# speech2.net
KiCad netlist of a schematic drawn in EAGLE
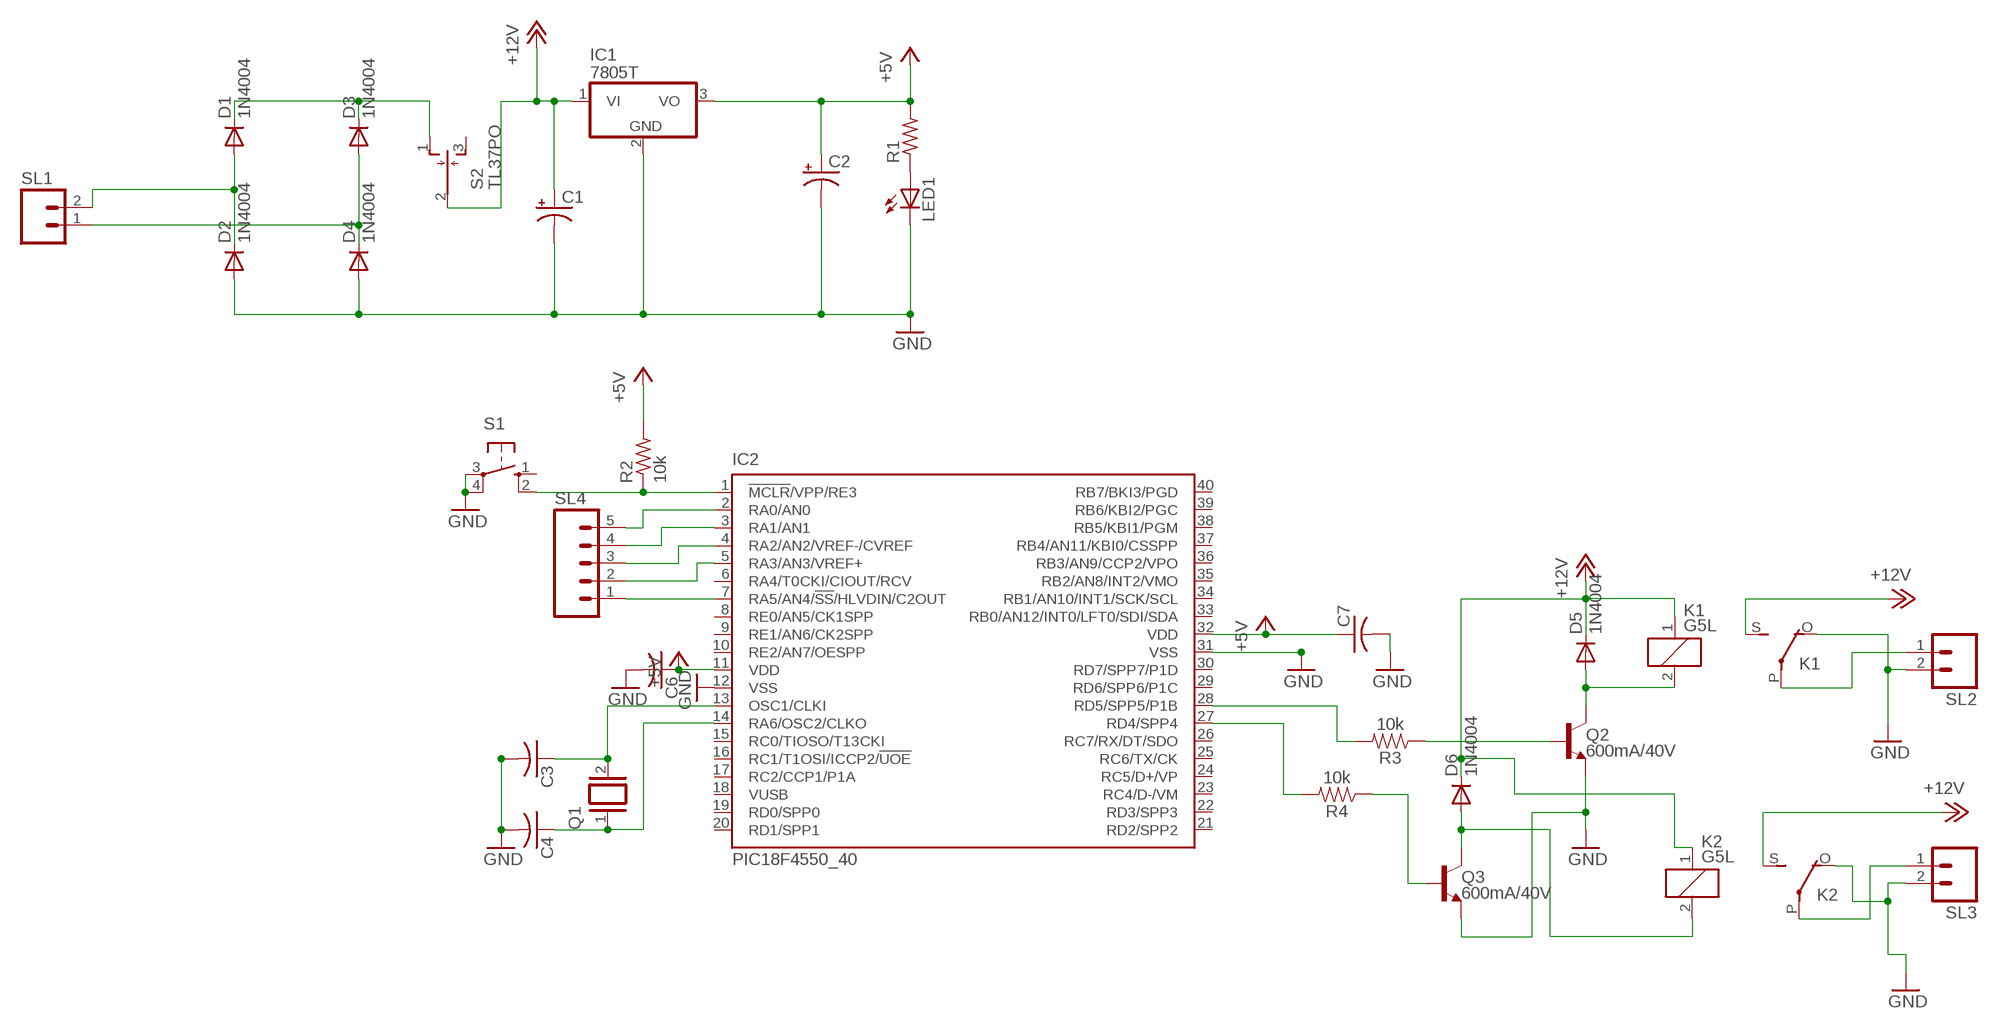
[diagram p0: schematic, sheet 1]

(export (version "E")
  (design (tool "Eeschema 10.0.6"))
  (components
    (comp (ref "C1")
      (value "CPOL-USE3.5-8")
      (footprint "eagle-import:E3,5-8")
      (libsource (lib "eagle-import") (part "CPOL-USE3.5-8"))
    )
    (comp (ref "C2")
      (value "CPOL-USE3.5-8")
      (footprint "eagle-import:E3,5-8")
      (libsource (lib "eagle-import") (part "CPOL-USE3.5-8"))
    )
    (comp (ref "C3")
      (value "C-US025-024X044")
      (footprint "eagle-import:C025-024X044")
      (libsource (lib "eagle-import") (part "C-US025-024X044"))
    )
    (comp (ref "C4")
      (value "C-US025-024X044")
      (footprint "eagle-import:C025-024X044")
      (libsource (lib "eagle-import") (part "C-US025-024X044"))
    )
    (comp (ref "C6")
      (value "C-US025-024X044")
      (footprint "eagle-import:C025-024X044")
      (libsource (lib "eagle-import") (part "C-US025-024X044"))
    )
    (comp (ref "C7")
      (value "C-US025-024X044")
      (footprint "eagle-import:C025-024X044")
      (libsource (lib "eagle-import") (part "C-US025-024X044"))
    )
    (comp (ref "D1")
      (value "1N4004")
      (footprint "eagle-import:DO41-10")
      (libsource (lib "eagle-import") (part "1N4004"))
    )
    (comp (ref "D2")
      (value "1N4004")
      (footprint "eagle-import:DO41-10")
      (libsource (lib "eagle-import") (part "1N4004"))
    )
    (comp (ref "D3")
      (value "1N4004")
      (footprint "eagle-import:DO41-10")
      (libsource (lib "eagle-import") (part "1N4004"))
    )
    (comp (ref "D4")
      (value "1N4004")
      (footprint "eagle-import:DO41-10")
      (libsource (lib "eagle-import") (part "1N4004"))
    )
    (comp (ref "D5")
      (value "1N4004")
      (footprint "eagle-import:DO41-10")
      (libsource (lib "eagle-import") (part "1N4004"))
    )
    (comp (ref "D6")
      (value "1N4004")
      (footprint "eagle-import:DO41-10")
      (libsource (lib "eagle-import") (part "1N4004"))
    )
    (comp (ref "IC1")
      (value "7805T")
      (footprint "eagle-import:TO220H")
      (libsource (lib "eagle-import") (part "78T05"))
    )
    (comp (ref "IC2")
      (value "PIC18F4550_40")
      (footprint "eagle-import:DIL40")
      (fields (field (name "MF") "MICROCHIP") (field (name "MPN") "PIC18F4550-I/P"))
      (libsource (lib "eagle-import") (part "PIC18F4_40550"))
    )
    (comp (ref "K1")
      (value "G5L")
      (footprint "eagle-import:G5LE")
      (libsource (lib "eagle-import") (part "G5L"))
    )
    (comp (ref "K2")
      (value "G5L")
      (footprint "eagle-import:G5LE")
      (libsource (lib "eagle-import") (part "G5L"))
    )
    (comp (ref "LED1")
      (value "LED5MM")
      (footprint "eagle-import:LED5MM")
      (libsource (lib "eagle-import") (part "LED5MM"))
    )
    (comp (ref "Q1")
      (value "XTAL/S")
      (footprint "eagle-import:QS")
      (libsource (lib "eagle-import") (part "XTAL/S"))
    )
    (comp (ref "Q2")
      (value "600mA/40V")
      (footprint "eagle-import:TO-92")
      (libsource (lib "eagle-import") (part "TRANS_NPN-P2N2222A"))
    )
    (comp (ref "Q3")
      (value "600mA/40V")
      (footprint "eagle-import:TO-92")
      (libsource (lib "eagle-import") (part "TRANS_NPN-P2N2222A"))
    )
    (comp (ref "R1")
      (value "R-US_0207/10")
      (footprint "eagle-import:0207_10")
      (libsource (lib "eagle-import") (part "R-US_0207/10"))
    )
    (comp (ref "R2")
      (value "10k")
      (footprint "eagle-import:0207_10")
      (libsource (lib "eagle-import") (part "R-US_0207/10"))
    )
    (comp (ref "R3")
      (value "10k")
      (footprint "eagle-import:AXIAL-0.3")
      (libsource (lib "eagle-import") (part "10KOHM-HORIZ-1/4W-1%"))
    )
    (comp (ref "R4")
      (value "10k")
      (footprint "eagle-import:AXIAL-0.3")
      (libsource (lib "eagle-import") (part "10KOHM-HORIZ-1/4W-1%"))
    )
    (comp (ref "S1")
      (value "10-XX")
      (footprint "eagle-import:B3F-10XX")
      (fields (field (name "MPN") "B3F-1000"))
      (libsource (lib "eagle-import") (part "10-XX"))
    )
    (comp (ref "S2")
      (value "TL37PO")
      (footprint "eagle-import:TL3XPO")
      (libsource (lib "eagle-import") (part "TL37PO"))
    )
    (comp (ref "SL1")
      (value "MA02")
      (footprint "eagle-import:02PA")
      (libsource (lib "eagle-import") (part "MA02"))
    )
    (comp (ref "SL2")
      (value "MA02")
      (footprint "eagle-import:02PA")
      (libsource (lib "eagle-import") (part "MA02"))
    )
    (comp (ref "SL3")
      (value "MA02")
      (footprint "eagle-import:02PA")
      (libsource (lib "eagle-import") (part "MA02"))
    )
    (comp (ref "SL4")
      (value "MA05")
      (footprint "eagle-import:05PA")
      (libsource (lib "eagle-import") (part "MA05"))
    )
  )
  (nets
    (net (code "1") (name "+5V") (class "Default")
      (node (ref "C2") (pin "+") (pinfunction "+_+") (pintype "passive"))
      (node (ref "C6") (pin "1") (pinfunction "1_1") (pintype "passive"))
      (node (ref "C7") (pin "1") (pinfunction "1_1") (pintype "passive"))
      (node (ref "IC1") (pin "3") (pinfunction "VO_3") (pintype "passive"))
      (node (ref "IC2") (pin "11") (pinfunction "VDD_11") (pintype "power_in"))
      (node (ref "IC2") (pin "32") (pinfunction "VDD_32") (pintype "power_in"))
      (node (ref "R1") (pin "2") (pinfunction "2_2") (pintype "passive"))
      (node (ref "R2") (pin "2") (pinfunction "2_2") (pintype "passive"))
    )
    (net (code "2") (name "+12V") (class "Default")
      (node (ref "C1") (pin "+") (pinfunction "+_+") (pintype "passive"))
      (node (ref "D5") (pin "C") (pinfunction "C_C") (pintype "passive"))
      (node (ref "D6") (pin "C") (pinfunction "C_C") (pintype "passive"))
      (node (ref "IC1") (pin "1") (pinfunction "VI_1") (pintype "input"))
      (node (ref "K1") (pin "1") (pinfunction "1_1") (pintype "passive"))
      (node (ref "K1") (pin "S") (pinfunction "S_S") (pintype "passive"))
      (node (ref "K2") (pin "1") (pinfunction "1_1") (pintype "passive"))
      (node (ref "K2") (pin "S") (pinfunction "S_S") (pintype "passive"))
      (node (ref "S2") (pin "2") (pinfunction "P_2") (pintype "passive"))
    )
    (net (code "3") (name "GND") (class "Default")
      (node (ref "C1") (pin "-") (pinfunction "-_-") (pintype "passive"))
      (node (ref "C2") (pin "-") (pinfunction "-_-") (pintype "passive"))
      (node (ref "C3") (pin "2") (pinfunction "2_2") (pintype "passive"))
      (node (ref "C4") (pin "2") (pinfunction "2_2") (pintype "passive"))
      (node (ref "C6") (pin "2") (pinfunction "2_2") (pintype "passive"))
      (node (ref "C7") (pin "2") (pinfunction "2_2") (pintype "passive"))
      (node (ref "D2") (pin "A") (pinfunction "A_A") (pintype "passive"))
      (node (ref "D4") (pin "A") (pinfunction "A_A") (pintype "passive"))
      (node (ref "IC1") (pin "2") (pinfunction "GND_2") (pintype "passive"))
      (node (ref "IC2") (pin "12") (pinfunction "VSS_12") (pintype "power_in"))
      (node (ref "IC2") (pin "31") (pinfunction "VSS_31") (pintype "power_in"))
      (node (ref "K1") (pin "O") (pinfunction "O_O") (pintype "passive"))
      (node (ref "K2") (pin "O") (pinfunction "O_O") (pintype "passive"))
      (node (ref "LED1") (pin "K") (pinfunction "C_K") (pintype "passive"))
      (node (ref "Q2") (pin "3") (pinfunction "E_3") (pintype "passive"))
      (node (ref "Q3") (pin "3") (pinfunction "E_3") (pintype "passive"))
      (node (ref "S1") (pin "3") (pinfunction "P_3") (pintype "passive"))
      (node (ref "S1") (pin "4") (pinfunction "P1_4") (pintype "passive"))
      (node (ref "SL2") (pin "2") (pinfunction "2_2") (pintype "passive"))
      (node (ref "SL3") (pin "2") (pinfunction "2_2") (pintype "passive"))
    )
    (net (code "4") (name "Net-(D1-PadA)") (class "Default")
      (node (ref "D1") (pin "A") (pinfunction "A_A") (pintype "passive"))
      (node (ref "D2") (pin "C") (pinfunction "C_C") (pintype "passive"))
      (node (ref "SL1") (pin "2") (pinfunction "2_2") (pintype "passive"))
    )
    (net (code "5") (name "Net-(D3-PadA)") (class "Default")
      (node (ref "D3") (pin "A") (pinfunction "A_A") (pintype "passive"))
      (node (ref "D4") (pin "C") (pinfunction "C_C") (pintype "passive"))
      (node (ref "SL1") (pin "1") (pinfunction "1_1") (pintype "passive"))
    )
    (net (code "6") (name "Net-(IC2-OSC1{slash}CLKI)") (class "Default")
      (node (ref "C3") (pin "1") (pinfunction "1_1") (pintype "passive"))
      (node (ref "IC2") (pin "13") (pinfunction "OSC1/CLKI_13") (pintype "input"))
      (node (ref "Q1") (pin "2") (pinfunction "2_2") (pintype "passive"))
    )
    (net (code "7") (name "Net-(IC2-RA0{slash}AN0)") (class "Default")
      (node (ref "IC2") (pin "2") (pinfunction "RA0/AN0_2") (pintype "bidirectional"))
      (node (ref "SL4") (pin "5") (pinfunction "5_5") (pintype "passive"))
    )
    (net (code "8") (name "Net-(IC2-RA1{slash}AN1)") (class "Default")
      (node (ref "IC2") (pin "3") (pinfunction "RA1/AN1_3") (pintype "bidirectional"))
      (node (ref "SL4") (pin "4") (pinfunction "4_4") (pintype "passive"))
    )
    (net (code "9") (name "Net-(IC2-RA2{slash}AN2{slash}VREF-{slash}CVREF)") (class "Default")
      (node (ref "IC2") (pin "4") (pinfunction "RA2/AN2/VREF-/CVREF_4") (pintype "bidirectional"))
      (node (ref "SL4") (pin "3") (pinfunction "3_3") (pintype "passive"))
    )
    (net (code "10") (name "Net-(IC2-RA3{slash}AN3{slash}VREF+)") (class "Default")
      (node (ref "IC2") (pin "5") (pinfunction "RA3/AN3/VREF+_5") (pintype "bidirectional"))
      (node (ref "SL4") (pin "2") (pinfunction "2_2") (pintype "passive"))
    )
    (net (code "11") (name "Net-(IC2-RA5{slash}AN4{slash}~{SS}{slash}HLVDIN{slash}C2OUT)") (class "Default")
      (node (ref "IC2") (pin "7") (pinfunction "RA5/AN4/~{SS}/HLVDIN/C2OUT_7") (pintype "bidirectional"))
      (node (ref "SL4") (pin "1") (pinfunction "1_1") (pintype "passive"))
    )
    (net (code "12") (name "Net-(IC2-RA6{slash}OSC2{slash}CLKO)") (class "Default")
      (node (ref "C4") (pin "1") (pinfunction "1_1") (pintype "passive"))
      (node (ref "IC2") (pin "14") (pinfunction "RA6/OSC2/CLKO_14") (pintype "output"))
      (node (ref "Q1") (pin "1") (pinfunction "1_1") (pintype "passive"))
    )
    (net (code "13") (name "Net-(IC2-RD4{slash}SPP4)") (class "Default")
      (node (ref "IC2") (pin "27") (pinfunction "RD4/SPP4_27") (pintype "bidirectional"))
      (node (ref "R4") (pin "P$2") (pinfunction "2_P$2") (pintype "passive"))
    )
    (net (code "14") (name "Net-(IC2-RD5{slash}SPP5{slash}P1B)") (class "Default")
      (node (ref "IC2") (pin "28") (pinfunction "RD5/SPP5/P1B_28") (pintype "bidirectional"))
      (node (ref "R3") (pin "P$2") (pinfunction "2_P$2") (pintype "passive"))
    )
    (net (code "15") (name "Net-(IC2-~{MCLR}{slash}VPP{slash}RE3)") (class "Default")
      (node (ref "IC2") (pin "1") (pinfunction "~{MCLR}/VPP/RE3_1") (pintype "input"))
      (node (ref "R2") (pin "1") (pinfunction "1_1") (pintype "passive"))
      (node (ref "S1") (pin "2") (pinfunction "S1_2") (pintype "passive"))
    )
    (net (code "16") (name "Net-(K1-PadP)") (class "Default")
      (node (ref "K1") (pin "P") (pinfunction "P_P") (pintype "passive"))
      (node (ref "SL2") (pin "1") (pinfunction "1_1") (pintype "passive"))
    )
    (net (code "17") (name "Net-(K2-PadP)") (class "Default")
      (node (ref "K2") (pin "P") (pinfunction "P_P") (pintype "passive"))
      (node (ref "SL3") (pin "1") (pinfunction "1_1") (pintype "passive"))
    )
    (net (code "18") (name "Net-(LED1-PadA)") (class "Default")
      (node (ref "LED1") (pin "A") (pinfunction "A_A") (pintype "passive"))
      (node (ref "R1") (pin "1") (pinfunction "1_1") (pintype "passive"))
    )
    (net (code "19") (name "Net-(Q2-B)") (class "Default")
      (node (ref "Q2") (pin "2") (pinfunction "B_2") (pintype "passive"))
      (node (ref "R3") (pin "P$1") (pinfunction "1_P$1") (pintype "passive"))
    )
    (net (code "20") (name "Net-(Q2-C)") (class "Default")
      (node (ref "D5") (pin "A") (pinfunction "A_A") (pintype "passive"))
      (node (ref "K1") (pin "2") (pinfunction "2_2") (pintype "passive"))
      (node (ref "Q2") (pin "1") (pinfunction "C_1") (pintype "passive"))
    )
    (net (code "21") (name "Net-(Q3-B)") (class "Default")
      (node (ref "Q3") (pin "2") (pinfunction "B_2") (pintype "passive"))
      (node (ref "R4") (pin "P$1") (pinfunction "1_P$1") (pintype "passive"))
    )
    (net (code "22") (name "Net-(Q3-C)") (class "Default")
      (node (ref "D6") (pin "A") (pinfunction "A_A") (pintype "passive"))
      (node (ref "K2") (pin "2") (pinfunction "2_2") (pintype "passive"))
      (node (ref "Q3") (pin "1") (pinfunction "C_1") (pintype "passive"))
    )
    (net (code "23") (name "Net-(S2-O)") (class "Default")
      (node (ref "D1") (pin "C") (pinfunction "C_C") (pintype "passive"))
      (node (ref "D3") (pin "C") (pinfunction "C_C") (pintype "passive"))
      (node (ref "S2") (pin "1") (pinfunction "O_1") (pintype "passive"))
    )
    (net (code "24") (name "unconnected-(IC2-RA4{slash}T0CKI{slash}CIOUT{slash}RCV-Pad6)") (class "Default")
      (node (ref "IC2") (pin "6") (pinfunction "RA4/T0CKI/CIOUT/RCV_6") (pintype "bidirectional"))
    )
    (net (code "25") (name "unconnected-(IC2-RB0{slash}AN12{slash}INT0{slash}LFT0{slash}SDI{slash}SDA-Pad33)") (class "Default")
      (node (ref "IC2") (pin "33") (pinfunction "RB0/AN12/INT0/LFT0/SDI/SDA_33") (pintype "bidirectional"))
    )
    (net (code "26") (name "unconnected-(IC2-RB1{slash}AN10{slash}INT1{slash}SCK{slash}SCL-Pad34)") (class "Default")
      (node (ref "IC2") (pin "34") (pinfunction "RB1/AN10/INT1/SCK/SCL_34") (pintype "bidirectional"))
    )
    (net (code "27") (name "unconnected-(IC2-RB2{slash}AN8{slash}INT2{slash}VMO-Pad35)") (class "Default")
      (node (ref "IC2") (pin "35") (pinfunction "RB2/AN8/INT2/VMO_35") (pintype "bidirectional"))
    )
    (net (code "28") (name "unconnected-(IC2-RB3{slash}AN9{slash}CCP2{slash}VPO-Pad36)") (class "Default")
      (node (ref "IC2") (pin "36") (pinfunction "RB3/AN9/CCP2/VPO_36") (pintype "bidirectional"))
    )
    (net (code "29") (name "unconnected-(IC2-RB4{slash}AN11{slash}KBI0{slash}CSSPP-Pad37)") (class "Default")
      (node (ref "IC2") (pin "37") (pinfunction "RB4/AN11/KBI0/CSSPP_37") (pintype "bidirectional"))
    )
    (net (code "30") (name "unconnected-(IC2-RB5{slash}KBI1{slash}PGM-Pad38)") (class "Default")
      (node (ref "IC2") (pin "38") (pinfunction "RB5/KBI1/PGM_38") (pintype "bidirectional"))
    )
    (net (code "31") (name "unconnected-(IC2-RB6{slash}KBI2{slash}PGC-Pad39)") (class "Default")
      (node (ref "IC2") (pin "39") (pinfunction "RB6/KBI2/PGC_39") (pintype "bidirectional"))
    )
    (net (code "32") (name "unconnected-(IC2-RB7{slash}BKI3{slash}PGD-Pad40)") (class "Default")
      (node (ref "IC2") (pin "40") (pinfunction "RB7/BKI3/PGD_40") (pintype "bidirectional"))
    )
    (net (code "33") (name "unconnected-(IC2-RC0{slash}TIOSO{slash}T13CKI-Pad15)") (class "Default")
      (node (ref "IC2") (pin "15") (pinfunction "RC0/TIOSO/T13CKI_15") (pintype "bidirectional"))
    )
    (net (code "34") (name "unconnected-(IC2-RC1{slash}T1OSI{slash}ICCP2{slash}~{UOE}-Pad16)") (class "Default")
      (node (ref "IC2") (pin "16") (pinfunction "RC1/T1OSI/ICCP2/~{UOE}_16") (pintype "bidirectional"))
    )
    (net (code "35") (name "unconnected-(IC2-RC2{slash}CCP1{slash}P1A-Pad17)") (class "Default")
      (node (ref "IC2") (pin "17") (pinfunction "RC2/CCP1/P1A_17") (pintype "bidirectional"))
    )
    (net (code "36") (name "unconnected-(IC2-RC4{slash}D-{slash}VM-Pad23)") (class "Default")
      (node (ref "IC2") (pin "23") (pinfunction "RC4/D-/VM_23") (pintype "bidirectional"))
    )
    (net (code "37") (name "unconnected-(IC2-RC5{slash}D+{slash}VP-Pad24)") (class "Default")
      (node (ref "IC2") (pin "24") (pinfunction "RC5/D+/VP_24") (pintype "bidirectional"))
    )
    (net (code "38") (name "unconnected-(IC2-RC6{slash}TX{slash}CK-Pad25)") (class "Default")
      (node (ref "IC2") (pin "25") (pinfunction "RC6/TX/CK_25") (pintype "bidirectional"))
    )
    (net (code "39") (name "unconnected-(IC2-RC7{slash}RX{slash}DT{slash}SDO-Pad26)") (class "Default")
      (node (ref "IC2") (pin "26") (pinfunction "RC7/RX/DT/SDO_26") (pintype "bidirectional"))
    )
    (net (code "40") (name "unconnected-(IC2-RD0{slash}SPP0-Pad19)") (class "Default")
      (node (ref "IC2") (pin "19") (pinfunction "RD0/SPP0_19") (pintype "bidirectional"))
    )
    (net (code "41") (name "unconnected-(IC2-RD1{slash}SPP1-Pad20)") (class "Default")
      (node (ref "IC2") (pin "20") (pinfunction "RD1/SPP1_20") (pintype "bidirectional"))
    )
    (net (code "42") (name "unconnected-(IC2-RD2{slash}SPP2-Pad21)") (class "Default")
      (node (ref "IC2") (pin "21") (pinfunction "RD2/SPP2_21") (pintype "bidirectional"))
    )
    (net (code "43") (name "unconnected-(IC2-RD3{slash}SPP3-Pad22)") (class "Default")
      (node (ref "IC2") (pin "22") (pinfunction "RD3/SPP3_22") (pintype "bidirectional"))
    )
    (net (code "44") (name "unconnected-(IC2-RD6{slash}SPP6{slash}P1C-Pad29)") (class "Default")
      (node (ref "IC2") (pin "29") (pinfunction "RD6/SPP6/P1C_29") (pintype "bidirectional"))
    )
    (net (code "45") (name "unconnected-(IC2-RD7{slash}SPP7{slash}P1D-Pad30)") (class "Default")
      (node (ref "IC2") (pin "30") (pinfunction "RD7/SPP7/P1D_30") (pintype "bidirectional"))
    )
    (net (code "46") (name "unconnected-(IC2-RE0{slash}AN5{slash}CK1SPP-Pad8)") (class "Default")
      (node (ref "IC2") (pin "8") (pinfunction "RE0/AN5/CK1SPP_8") (pintype "bidirectional"))
    )
    (net (code "47") (name "unconnected-(IC2-RE1{slash}AN6{slash}CK2SPP-Pad9)") (class "Default")
      (node (ref "IC2") (pin "9") (pinfunction "RE1/AN6/CK2SPP_9") (pintype "bidirectional"))
    )
    (net (code "48") (name "unconnected-(IC2-RE2{slash}AN7{slash}OESPP-Pad10)") (class "Default")
      (node (ref "IC2") (pin "10") (pinfunction "RE2/AN7/OESPP_10") (pintype "bidirectional"))
    )
    (net (code "49") (name "unconnected-(IC2-VUSB-Pad18)") (class "Default")
      (node (ref "IC2") (pin "18") (pinfunction "VUSB_18") (pintype "bidirectional"))
    )
    (net (code "50") (name "unconnected-(S1-S-Pad1)") (class "Default")
      (node (ref "S1") (pin "1") (pinfunction "S_1") (pintype "passive"))
    )
    (net (code "51") (name "unconnected-(S2-S-Pad3)") (class "Default")
      (node (ref "S2") (pin "3") (pinfunction "S_3") (pintype "passive"))
    )
  )
)
